# ANALOG-PART.net
KiCad netlist of a schematic drawn in Altium Designer
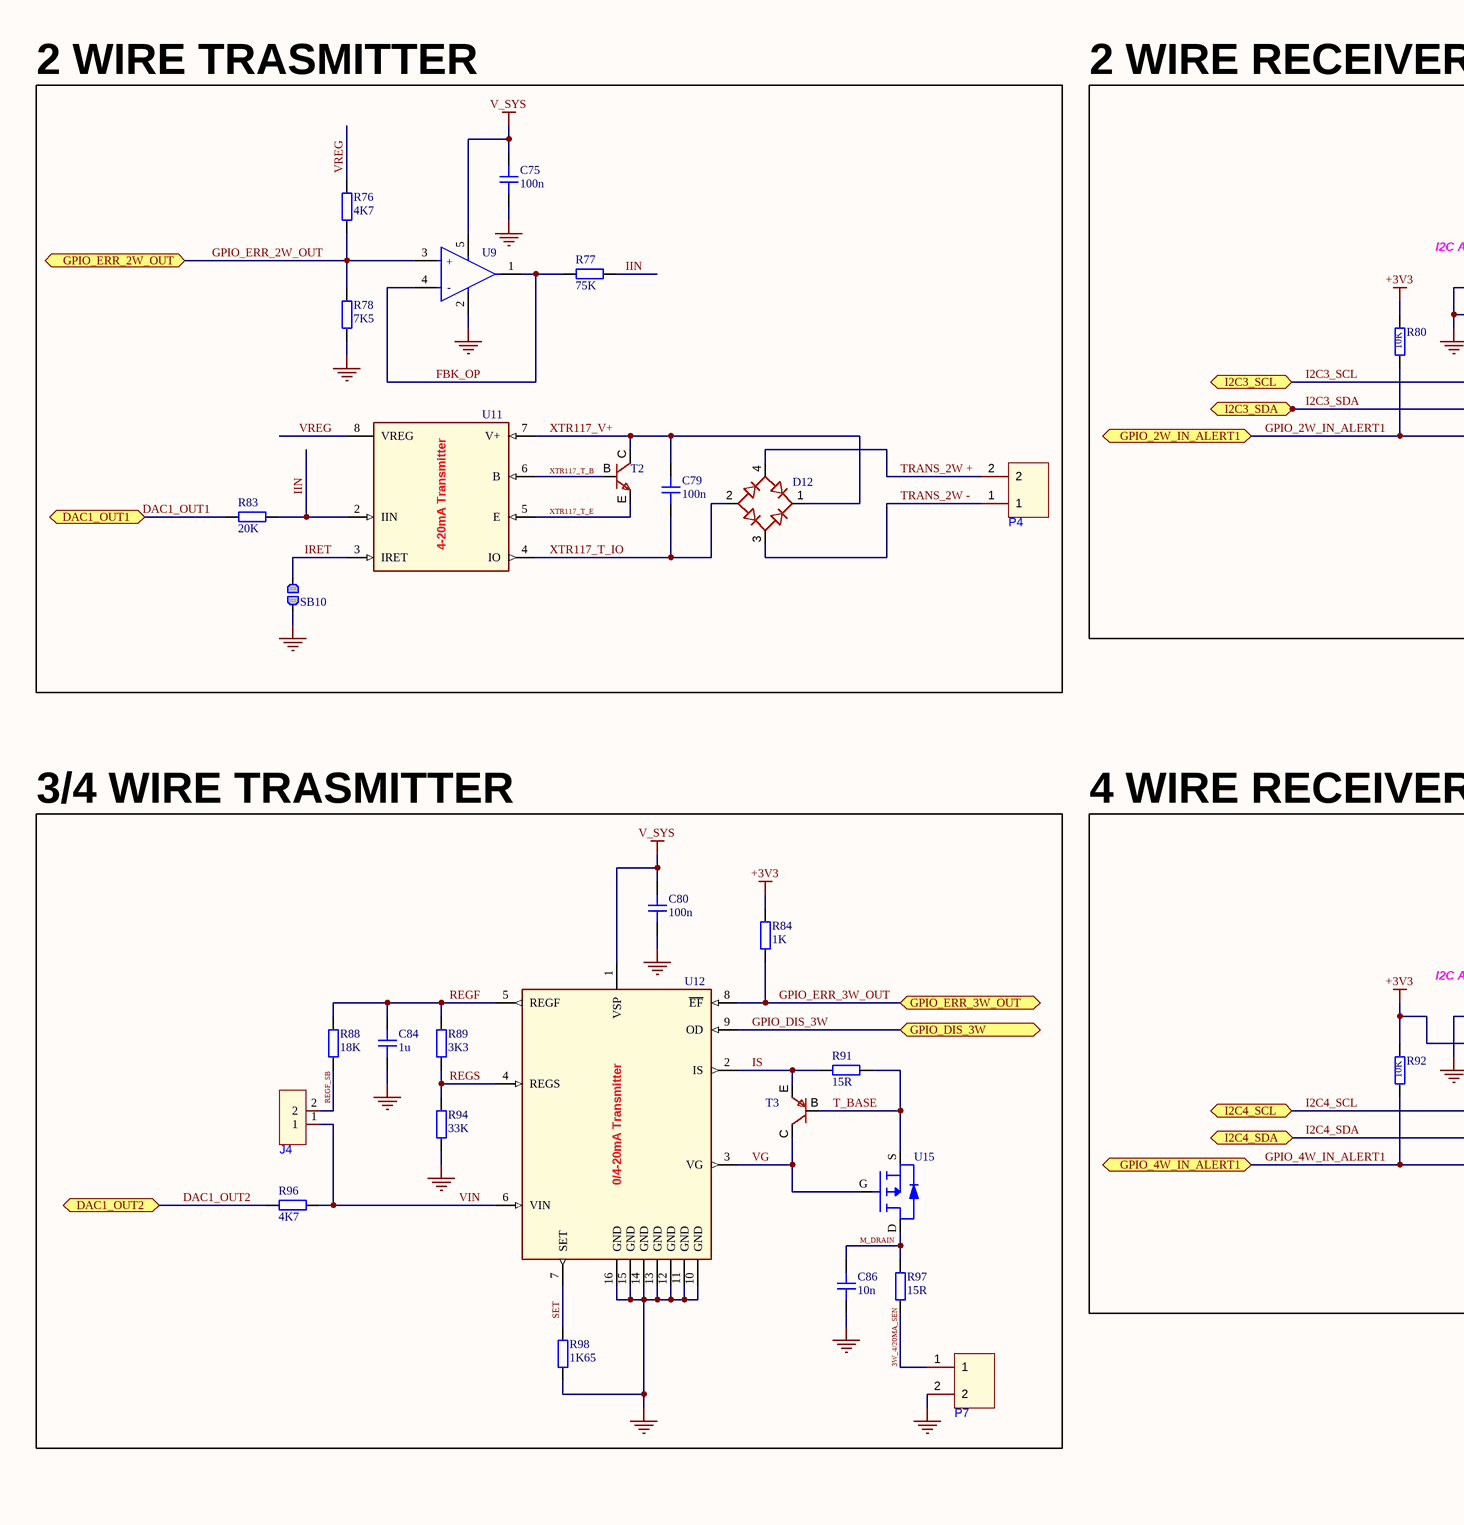
[diagram p0: ANALOG-PART.SchDoc, left]
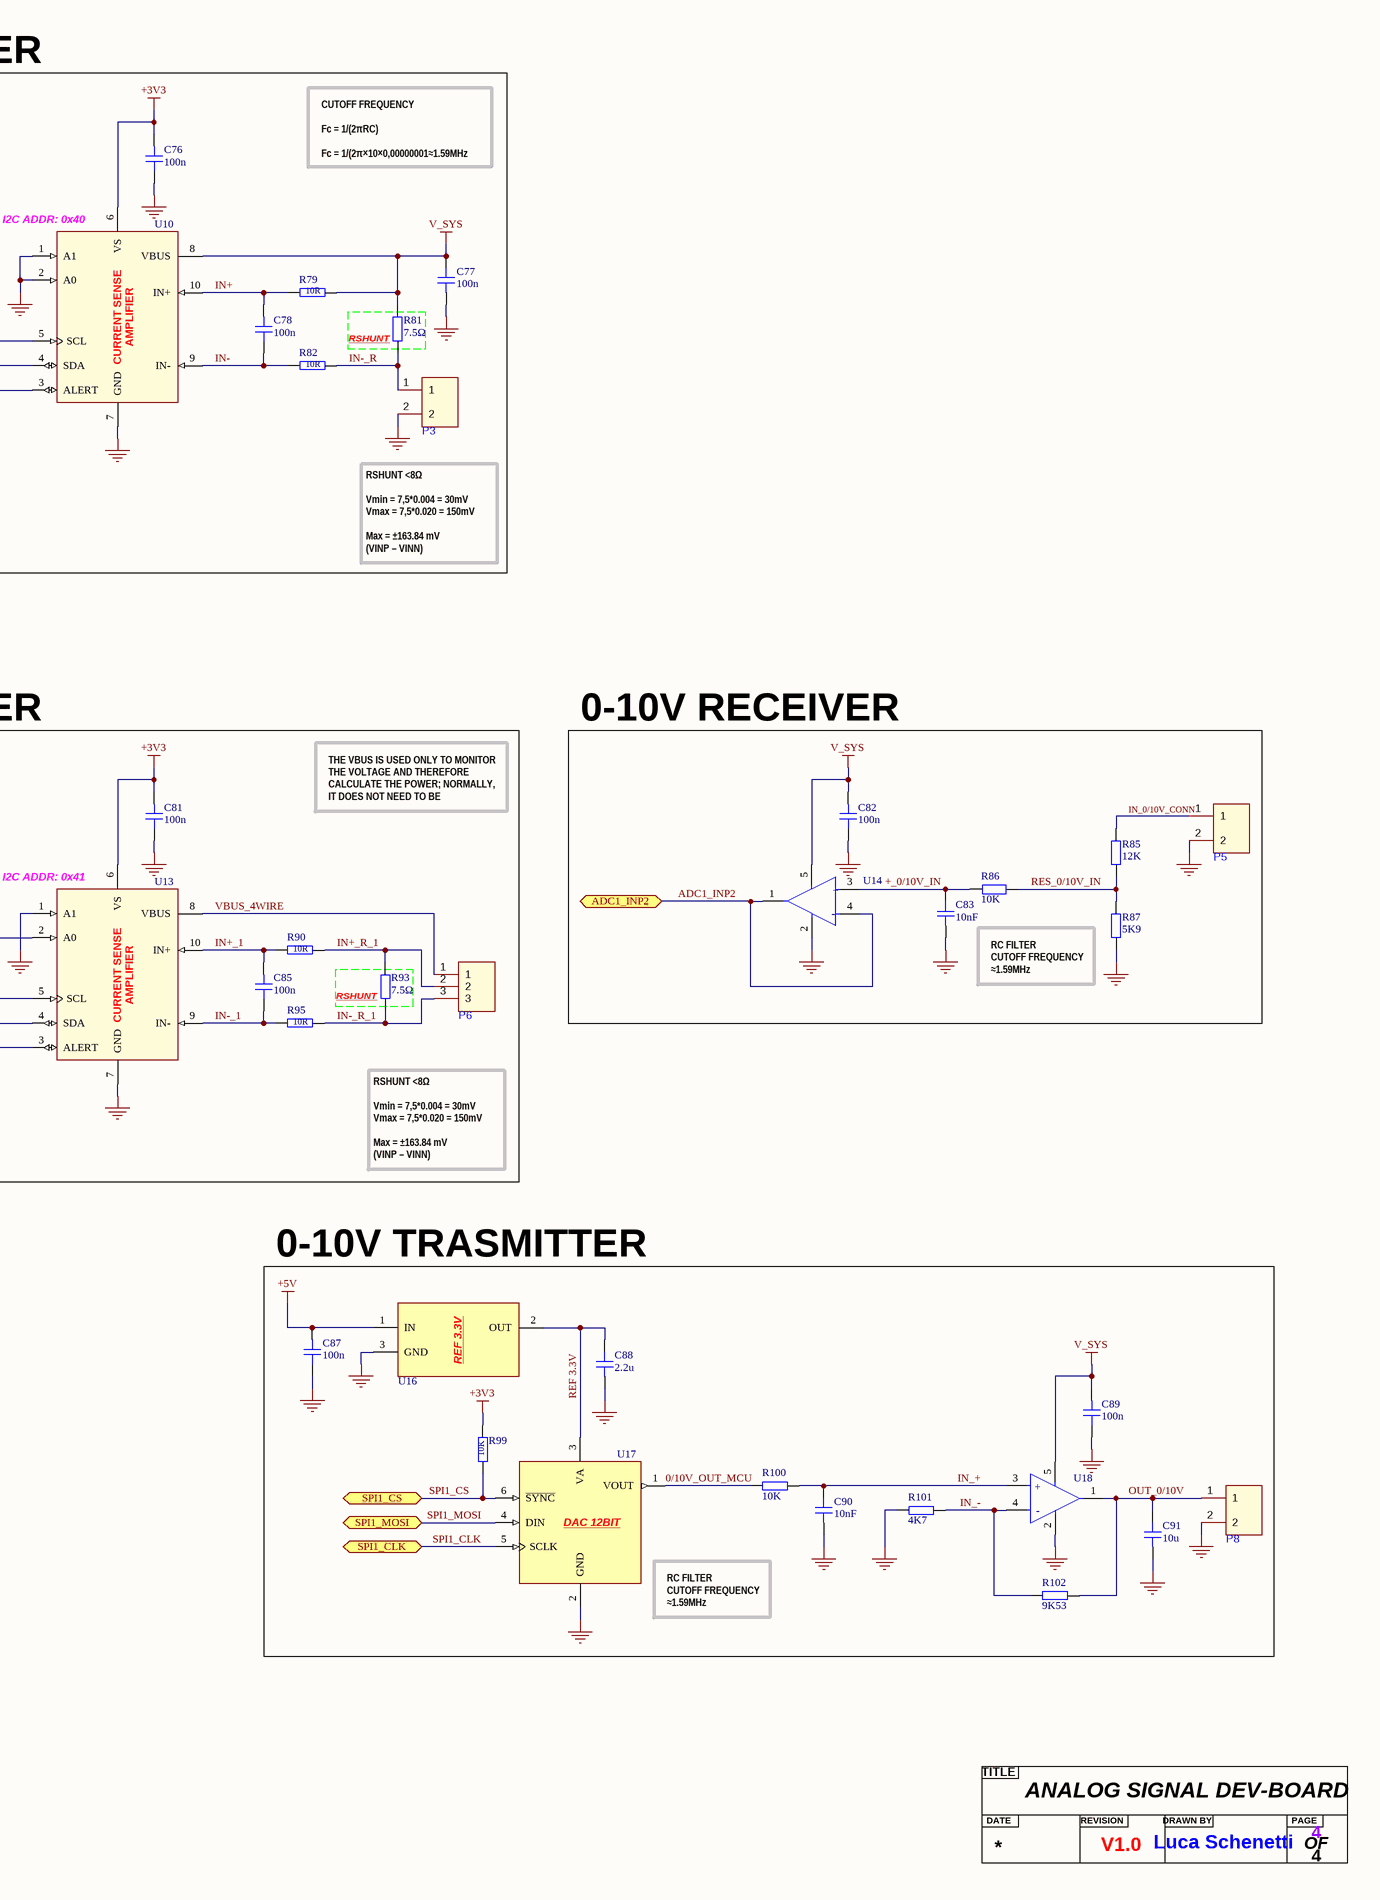
[diagram p1: ANALOG-PART.SchDoc, right]

(export (version "E")
  (design (tool "Eeschema 10.0.6"))
  (components
    (comp (ref "C75")
      (value "100n")
      (footprint "CAP_0603")
      (description "Capacitor SMD 0603 [C14663]")
      (libsource (lib "Schematic-Lib-PhilsLab") (part "CAP_0603"))
    )
    (comp (ref "C76")
      (value "100n")
      (footprint "CAP_0603")
      (description "Capacitor SMD 0603 [C14663]")
      (libsource (lib "Schematic-Lib-PhilsLab") (part "CAP_0603"))
    )
    (comp (ref "C77")
      (value "100n")
      (footprint "CAP_0603")
      (description "Capacitor SMD 0603 [C14663]")
      (libsource (lib "Schematic-Lib-PhilsLab") (part "CAP_0603"))
    )
    (comp (ref "C78")
      (value "100n")
      (footprint "CAP_0603")
      (description "Capacitor SMD 0603 [C14663]")
      (libsource (lib "Schematic-Lib-PhilsLab") (part "CAP_0603"))
    )
    (comp (ref "C79")
      (value "100n")
      (footprint "CAP_0603")
      (description "Capacitor SMD 0603 [C14663]")
      (libsource (lib "Schematic-Lib-PhilsLab") (part "CAP_0603"))
    )
    (comp (ref "C80")
      (value "100n")
      (footprint "CAP_0603")
      (description "Capacitor SMD 0603 [C14663]")
      (libsource (lib "Schematic-Lib-PhilsLab") (part "CAP_0603"))
    )
    (comp (ref "C81")
      (value "100n")
      (footprint "CAP_0603")
      (description "Capacitor SMD 0603 [C14663]")
      (libsource (lib "Schematic-Lib-PhilsLab") (part "CAP_0603"))
    )
    (comp (ref "C82")
      (value "100n")
      (footprint "CAP_0603")
      (description "Capacitor SMD 0603 [C14663]")
      (libsource (lib "Schematic-Lib-PhilsLab") (part "CAP_0603"))
    )
    (comp (ref "C83")
      (value "10nF")
      (footprint "CAP_0603")
      (description "[C302009]")
      (libsource (lib "Schematic-Lib-PhilsLab") (part "CAP_0603"))
    )
    (comp (ref "C84")
      (value "1u")
      (footprint "CAP_0603")
      (description "[C15849]")
      (libsource (lib "Schematic-Lib-PhilsLab") (part "CAP_0603"))
    )
    (comp (ref "C85")
      (value "100n")
      (footprint "CAP_0603")
      (description "Capacitor SMD 0603 [C14663]")
      (libsource (lib "Schematic-Lib-PhilsLab") (part "CAP_0603"))
    )
    (comp (ref "C86")
      (value "10n")
      (footprint "CAP_0603")
      (description "[C302009]")
      (libsource (lib "Schematic-Lib-PhilsLab") (part "CAP_0603"))
    )
    (comp (ref "C87")
      (value "100n")
      (footprint "CAP_0603")
      (description "Capacitor SMD 0603 [C14663]")
      (libsource (lib "Schematic-Lib-PhilsLab") (part "CAP_0603"))
    )
    (comp (ref "C88")
      (value "2.2u")
      (footprint "CAP_0603")
      (description "Capacitor SMD 0603 [C23630]")
      (libsource (lib "Schematic-Lib-PhilsLab") (part "CAP_0603"))
    )
    (comp (ref "C89")
      (value "100n")
      (footprint "CAP_0603")
      (description "Capacitor SMD 0603 [C14663]")
      (libsource (lib "Schematic-Lib-PhilsLab") (part "CAP_0603"))
    )
    (comp (ref "C90")
      (value "10nF")
      (footprint "CAP_0603")
      (description "[C302009]")
      (libsource (lib "Schematic-Lib-PhilsLab") (part "CAP_0603"))
    )
    (comp (ref "C91")
      (value "10u")
      (footprint "CAP_0603")
      (description "[C96446]")
      (libsource (lib "Schematic-Lib-PhilsLab") (part "CAP_0603"))
    )
    (comp (ref "D12")
      (value "MBS Bridge Rectifiers 35A 1.1V")
      (footprint "MB10S")
      (description "[C2488]")
      (libsource (lib "My_Library") (part "MB10S"))
    )
    (comp (ref "J4")
      (value "2.54mm 2P")
      (footprint "2.54mm 2P")
      (description "[C124375]")
      (fields (field (name "MANUFACTURER") "Ckmtw(灿科盟)") (field (name "MANUFACTURER PART") "B-2100S02P-A110"))
      (libsource (lib "My_Library") (part "2.54mm 2P"))
    )
    (comp (ref "P3")
      (value "WJ500V-5.08-2P")
      (footprint "CONN-TH_2P-P5.00_WJ500V-5.08-2P")
      (description "[C8465]")
      (fields (field (name "MANUFACTURER") "KANGNEX(康奈克斯电气)"))
      (libsource (lib "My_Library") (part "WJ500V-5.08-2P"))
    )
    (comp (ref "P4")
      (value "WJ500V-5.08-2P")
      (footprint "CONN-TH_2P-P5.00_WJ500V-5.08-2P")
      (description "[C8465]")
      (fields (field (name "MANUFACTURER") "KANGNEX(康奈克斯电气)"))
      (libsource (lib "") (part "WJ500V-5.08-2P_1"))
    )
    (comp (ref "P5")
      (value "WJ500V-5.08-2P")
      (footprint "CONN-TH_2P-P5.00_WJ500V-5.08-2P")
      (description "[C8465]")
      (fields (field (name "MANUFACTURER") "KANGNEX(康奈克斯电气)"))
      (libsource (lib "My_Library") (part "WJ500V-5.08-2P"))
    )
    (comp (ref "P6")
      (value "WJ500V-5.08-3P")
      (footprint "CONN-TH_3P-P5.00_WJ500V-5.08-3P")
      (description "[C72334]")
      (fields (field (name "MANUFACTURER") "KANGNEX(康奈克斯电气)"))
      (libsource (lib "My_Library") (part "WJ500V-5.08-3P"))
    )
    (comp (ref "P7")
      (value "WJ500V-5.08-2P")
      (footprint "CONN-TH_2P-P5.00_WJ500V-5.08-2P")
      (description "[C8465]")
      (fields (field (name "MANUFACTURER") "KANGNEX(康奈克斯电气)"))
      (libsource (lib "My_Library") (part "WJ500V-5.08-2P"))
    )
    (comp (ref "P8")
      (value "WJ500V-5.08-2P")
      (footprint "CONN-TH_2P-P5.00_WJ500V-5.08-2P")
      (description "[C8465]")
      (fields (field (name "MANUFACTURER") "KANGNEX(康奈克斯电气)"))
      (libsource (lib "My_Library") (part "WJ500V-5.08-2P"))
    )
    (comp (ref "R76")
      (value "4K7")
      (footprint "RES_0603")
      (description "[C105428]")
      (libsource (lib "Schematic-Lib-PhilsLab") (part "RES_0603"))
    )
    (comp (ref "R77")
      (value "75K")
      (footprint "RES_0603")
      (description "[C23242]")
      (libsource (lib "Schematic-Lib-PhilsLab") (part "RES_0603"))
    )
    (comp (ref "R78")
      (value "7K5")
      (footprint "RES_0603")
      (description "[C23234]")
      (libsource (lib "Schematic-Lib-PhilsLab") (part "RES_0603"))
    )
    (comp (ref "R79")
      (value "10R")
      (footprint "RES_0603")
      (description "Resistor SMD 0603 [C22859]")
      (libsource (lib "Schematic-Lib-PhilsLab") (part "RES_0603"))
    )
    (comp (ref "R80")
      (value "10K")
      (footprint "RES_0603")
      (description "[C25804]")
      (libsource (lib "Schematic-Lib-PhilsLab") (part "RES_0603"))
    )
    (comp (ref "R81")
      (value "7.5Ω")
      (footprint "RES_0805")
      (description "[C2828733]")
      (libsource (lib "Schematic-Lib-PhilsLab") (part "RES_0805"))
    )
    (comp (ref "R82")
      (value "10R")
      (footprint "RES_0603")
      (description "Resistor SMD 0603 [C22859]")
      (libsource (lib "Schematic-Lib-PhilsLab") (part "RES_0603"))
    )
    (comp (ref "R83")
      (value "20K")
      (footprint "RES_0603")
      (description "[C4184]")
      (libsource (lib "Schematic-Lib-PhilsLab") (part "RES_0603"))
    )
    (comp (ref "R84")
      (value "1K")
      (footprint "RES_0603")
      (description "[C21190]")
      (libsource (lib "Schematic-Lib-PhilsLab") (part "RES_0603"))
    )
    (comp (ref "R85")
      (value "12K")
      (footprint "RES_0603")
      (description "[C326735]")
      (libsource (lib "Schematic-Lib-PhilsLab") (part "RES_0603"))
    )
    (comp (ref "R86")
      (value "10K")
      (footprint "RES_0603")
      (description "[C25804]")
      (libsource (lib "Schematic-Lib-PhilsLab") (part "RES_0603"))
    )
    (comp (ref "R87")
      (value "5K9")
      (footprint "RES_0603")
      (description "[C491142]")
      (libsource (lib "Schematic-Lib-PhilsLab") (part "RES_0603"))
    )
    (comp (ref "R88")
      (value "18K")
      (footprint "RES_0603")
      (description "[C309650]")
      (libsource (lib "Schematic-Lib-PhilsLab") (part "RES_0603"))
    )
    (comp (ref "R89")
      (value "3K3")
      (footprint "RES_0603")
      (description "[C22978]")
      (libsource (lib "Schematic-Lib-PhilsLab") (part "RES_0603"))
    )
    (comp (ref "R90")
      (value "10R")
      (footprint "RES_0603")
      (description "Resistor SMD 0603 [C22859]")
      (libsource (lib "Schematic-Lib-PhilsLab") (part "RES_0603"))
    )
    (comp (ref "R91")
      (value "15R")
      (footprint "RES_0603")
      (description "[C22810]")
      (libsource (lib "Schematic-Lib-PhilsLab") (part "RES_0603"))
    )
    (comp (ref "R92")
      (value "10K")
      (footprint "RES_0603")
      (description "[C25804]")
      (libsource (lib "Schematic-Lib-PhilsLab") (part "RES_0603"))
    )
    (comp (ref "R93")
      (value "7.5Ω")
      (footprint "RES_0805")
      (description "[C2828733]")
      (libsource (lib "Schematic-Lib-PhilsLab") (part "RES_0805"))
    )
    (comp (ref "R94")
      (value "33K")
      (footprint "RES_0603")
      (description "[C4216]")
      (libsource (lib "Schematic-Lib-PhilsLab") (part "RES_0603"))
    )
    (comp (ref "R95")
      (value "10R")
      (footprint "RES_0603")
      (description "Resistor SMD 0603 [C22859]")
      (libsource (lib "Schematic-Lib-PhilsLab") (part "RES_0603"))
    )
    (comp (ref "R96")
      (value "4K7")
      (footprint "RES_0603")
      (description "[C99782]")
      (libsource (lib "Schematic-Lib-PhilsLab") (part "RES_0603"))
    )
    (comp (ref "R97")
      (value "15R")
      (footprint "RES_0603")
      (description "[C22810]")
      (libsource (lib "Schematic-Lib-PhilsLab") (part "RES_0603"))
    )
    (comp (ref "R98")
      (value "1K65")
      (footprint "RES_0603")
      (description "[C22845]")
      (libsource (lib "Schematic-Lib-PhilsLab") (part "RES_0603"))
    )
    (comp (ref "R99")
      (value "10K")
      (footprint "RES_0603")
      (description "[C25804]")
      (libsource (lib "Schematic-Lib-PhilsLab") (part "RES_0603"))
    )
    (comp (ref "R100")
      (value "10K")
      (footprint "RES_0603")
      (description "[C25804]")
      (libsource (lib "Schematic-Lib-PhilsLab") (part "RES_0603"))
    )
    (comp (ref "R101")
      (value "4K7")
      (footprint "RES_0603")
      (description "[C105428]")
      (libsource (lib "Schematic-Lib-PhilsLab") (part "RES_0603"))
    )
    (comp (ref "R102")
      (value "9K53")
      (footprint "RES_0603")
      (description "[C2960722]")
      (libsource (lib "Schematic-Lib-PhilsLab") (part "RES_0603"))
    )
    (comp (ref "SB10")
      (value "Solderbridge")
      (footprint "PCB_Mechanical:Solderbridge")
      (libsource (lib "SCH_Mechanical") (part "Solderbridge"))
    )
    (comp (ref "T2")
      (value "45V NPN IC = 2A")
      (footprint "FCX690BTA")
      (description "[C460072]")
      (libsource (lib "My_Library") (part "FCX690BTA"))
    )
    (comp (ref "T3")
      (value "25V PNP IC = 1,5A")
      (footprint "SS8550")
      (description "[C7420371]")
      (libsource (lib "My_Library") (part "SS8550"))
    )
    (comp (ref "U9")
      (value "OPA197IDBVR")
      (footprint "FP-DBV0005A-IPC_A")
      (description "IC OPAMP GP 1 CIRCUIT SOT23-5 [C221351]")
      (libsource (lib "Altium Content Vault") (part "1dcd28e651784f0a5a8ed6f8452eeff"))
    )
    (comp (ref "U10")
      (value "Current Sense Amplifiers")
      (footprint "INA237AIDGSR")
      (description "[C2864837]")
      (libsource (lib "My_Library") (part "INA237AIDGSR"))
    )
    (comp (ref "U11")
      (value "4-20mA Current Loop Transmitter")
      (footprint "XTR117AIDGKR")
      (description "[C140927]")
      (libsource (lib "My_Library") (part "XTR117AIDGKR"))
    )
    (comp (ref "U12")
      (value "0/4-20mA Current Loop Transmitter")
      (footprint "XTR111AIDGQR")
      (description "[C26350]")
      (libsource (lib "My_Library") (part "XTR111AIDGQR"))
    )
    (comp (ref "U13")
      (value "Current Sense Amplifiers")
      (footprint "INA237AIDGSR")
      (description "[C2864837]")
      (libsource (lib "My_Library") (part "INA237AIDGSR"))
    )
    (comp (ref "U14")
      (value "OPA197IDBVR")
      (footprint "FP-DBV0005A-IPC_A")
      (description "[C221351]")
      (libsource (lib "Altium Content Vault") (part "1dcd28e651784f0a5a8ed6f8452eeff"))
    )
    (comp (ref "U15")
      (value "P-Channel Mosfet Vds=-60V Vgs=-20V")
      (footprint "SI2309CDS-T1-GE3")
      (description "[C5350873]")
      (libsource (lib "My_Library") (part "SI2309CDS-T1-GE3"))
    )
    (comp (ref "U16")
      (value "REF 3.3V")
      (footprint "REF3033AIDBZR")
      (description "[C36658]")
      (libsource (lib "My_Library") (part "REF3033AIDBZR"))
    )
    (comp (ref "U17")
      (value "DAC 12BIT")
      (footprint "DAC121S101CIMK/NOPB")
      (description "[C81724]")
      (libsource (lib "My_Library") (part "DAC121S101CIMK/NOPB"))
    )
    (comp (ref "U18")
      (value "OPA197IDBVR")
      (footprint "FP-DBV0005A-IPC_A")
      (description "[C221351]")
      (libsource (lib "Altium Content Vault") (part "1dcd28e651784f0a5a8ed6f8452eeff"))
    )
  )
  (nets
    (net (code "1") (name "+3V3") (class "Default")
      (node (ref "C76") (pin "1") (pinfunction "1_1") (pintype "passive"))
      (node (ref "C81") (pin "1") (pinfunction "1_1") (pintype "passive"))
      (node (ref "R80") (pin "2") (pinfunction "2_2") (pintype "passive"))
      (node (ref "R84") (pin "2") (pinfunction "2_2") (pintype "passive"))
      (node (ref "R92") (pin "2") (pinfunction "2_2") (pintype "passive"))
      (node (ref "R99") (pin "2") (pinfunction "2_2") (pintype "passive"))
      (node (ref "U10") (pin "6") (pinfunction "VS_6") (pintype "power_in"))
      (node (ref "U13") (pin "2") (pinfunction "A0_2") (pintype "input"))
      (node (ref "U13") (pin "6") (pinfunction "VS_6") (pintype "power_in"))
    )
    (net (code "2") (name "+5V") (class "Default")
      (node (ref "C87") (pin "1") (pinfunction "1_1") (pintype "passive"))
      (node (ref "U16") (pin "1") (pinfunction "IN_1") (pintype "power_in"))
    )
    (net (code "3") (name "/+_0{slash}10V_IN") (class "Default")
      (node (ref "C83") (pin "2") (pinfunction "2_2") (pintype "passive"))
      (node (ref "R86") (pin "2") (pinfunction "2_2") (pintype "passive"))
      (node (ref "U14") (pin "3") (pinfunction "+IN_3") (pintype "tri_state"))
    )
    (net (code "4") (name "/0{slash}10V_OUT_MCU") (class "Default")
      (node (ref "R100") (pin "1") (pinfunction "1_1") (pintype "passive"))
      (node (ref "U17") (pin "1") (pinfunction "VOUT_1") (pintype "output"))
    )
    (net (code "5") (name "/3W_4{slash}20MA_SEN") (class "Default")
      (node (ref "P7") (pin "1") (pinfunction "1_1") (pintype "passive"))
      (node (ref "R97") (pin "1") (pinfunction "1_1") (pintype "passive"))
    )
    (net (code "6") (name "/ADC1_INP2") (class "Default")
      (node (ref "U14") (pin "1") (pinfunction "OUT_1") (pintype "passive"))
      (node (ref "U14") (pin "4") (pinfunction "-IN_4") (pintype "tri_state"))
    )
    (net (code "7") (name "/DAC1_OUT1") (class "Default")
      (node (ref "R83") (pin "1") (pinfunction "1_1") (pintype "passive"))
    )
    (net (code "8") (name "/DAC1_OUT2") (class "Default")
      (node (ref "R96") (pin "1") (pinfunction "1_1") (pintype "passive"))
    )
    (net (code "9") (name "/FBK_OP") (class "Default")
      (node (ref "R77") (pin "1") (pinfunction "1_1") (pintype "passive"))
      (node (ref "U9") (pin "1") (pinfunction "OUT_1") (pintype "passive"))
      (node (ref "U9") (pin "4") (pinfunction "-IN_4") (pintype "tri_state"))
    )
    (net (code "10") (name "/GPIO_2W_IN_ALERT1") (class "Default")
      (node (ref "R80") (pin "1") (pinfunction "1_1") (pintype "passive"))
      (node (ref "U10") (pin "3") (pinfunction "ALERT_3") (pintype "bidirectional"))
    )
    (net (code "11") (name "/GPIO_4W_IN_ALERT1") (class "Default")
      (node (ref "R92") (pin "1") (pinfunction "1_1") (pintype "passive"))
      (node (ref "U13") (pin "3") (pinfunction "ALERT_3") (pintype "bidirectional"))
    )
    (net (code "12") (name "/GPIO_DIS_3W") (class "Default")
      (node (ref "U12") (pin "9") (pinfunction "OD_9") (pintype "input"))
    )
    (net (code "13") (name "/GPIO_ERR_2W_OUT") (class "Default")
      (node (ref "R76") (pin "1") (pinfunction "1_1") (pintype "passive"))
      (node (ref "R78") (pin "2") (pinfunction "2_2") (pintype "passive"))
      (node (ref "U9") (pin "3") (pinfunction "+IN_3") (pintype "tri_state"))
    )
    (net (code "14") (name "/GPIO_ERR_3W_OUT") (class "Default")
      (node (ref "R84") (pin "1") (pinfunction "1_1") (pintype "passive"))
      (node (ref "U12") (pin "8") (pinfunction "~{EF}_8") (pintype "input"))
    )
    (net (code "15") (name "/I2C3_SCL") (class "Default")
      (node (ref "U10") (pin "5") (pinfunction "SCL_5") (pintype "input"))
    )
    (net (code "16") (name "/I2C3_SDA") (class "Default")
      (node (ref "U10") (pin "4") (pinfunction "SDA_4") (pintype "bidirectional"))
    )
    (net (code "17") (name "/I2C4_SCL") (class "Default")
      (node (ref "U13") (pin "5") (pinfunction "SCL_5") (pintype "input"))
    )
    (net (code "18") (name "/I2C4_SDA") (class "Default")
      (node (ref "U13") (pin "4") (pinfunction "SDA_4") (pintype "bidirectional"))
    )
    (net (code "19") (name "/IIN") (class "Default")
      (node (ref "R77") (pin "2") (pinfunction "2_2") (pintype "passive"))
      (node (ref "R83") (pin "2") (pinfunction "2_2") (pintype "passive"))
      (node (ref "U11") (pin "2") (pinfunction "IIN_2") (pintype "input"))
    )
    (net (code "20") (name "/IN+") (class "Default")
      (node (ref "C78") (pin "1") (pinfunction "1_1") (pintype "passive"))
      (node (ref "R79") (pin "1") (pinfunction "1_1") (pintype "passive"))
      (node (ref "U10") (pin "10") (pinfunction "IN+_10") (pintype "input"))
    )
    (net (code "21") (name "/IN+_1") (class "Default")
      (node (ref "C85") (pin "1") (pinfunction "1_1") (pintype "passive"))
      (node (ref "R90") (pin "1") (pinfunction "1_1") (pintype "passive"))
      (node (ref "U13") (pin "10") (pinfunction "IN+_10") (pintype "input"))
    )
    (net (code "22") (name "/IN+_R_1") (class "Default")
      (node (ref "P6") (pin "2") (pinfunction "2_2") (pintype "passive"))
      (node (ref "R90") (pin "2") (pinfunction "2_2") (pintype "passive"))
      (node (ref "R93") (pin "2") (pinfunction "2_2") (pintype "passive"))
    )
    (net (code "23") (name "/IN-") (class "Default")
      (node (ref "C78") (pin "2") (pinfunction "2_2") (pintype "passive"))
      (node (ref "R82") (pin "1") (pinfunction "1_1") (pintype "passive"))
      (node (ref "U10") (pin "9") (pinfunction "IN-_9") (pintype "input"))
    )
    (net (code "24") (name "/IN-_1") (class "Default")
      (node (ref "C85") (pin "2") (pinfunction "2_2") (pintype "passive"))
      (node (ref "R95") (pin "1") (pinfunction "1_1") (pintype "passive"))
      (node (ref "U13") (pin "9") (pinfunction "IN-_9") (pintype "input"))
    )
    (net (code "25") (name "/IN-_R") (class "Default")
      (node (ref "P3") (pin "1") (pinfunction "1_1") (pintype "passive"))
      (node (ref "R81") (pin "1") (pinfunction "1_1") (pintype "passive"))
      (node (ref "R82") (pin "2") (pinfunction "2_2") (pintype "passive"))
    )
    (net (code "26") (name "/IN-_R_1") (class "Default")
      (node (ref "P6") (pin "3") (pinfunction "3_3") (pintype "passive"))
      (node (ref "R93") (pin "1") (pinfunction "1_1") (pintype "passive"))
      (node (ref "R95") (pin "2") (pinfunction "2_2") (pintype "passive"))
    )
    (net (code "27") (name "/IN_+") (class "Default")
      (node (ref "C90") (pin "2") (pinfunction "2_2") (pintype "passive"))
      (node (ref "R100") (pin "2") (pinfunction "2_2") (pintype "passive"))
      (node (ref "U18") (pin "3") (pinfunction "+IN_3") (pintype "tri_state"))
    )
    (net (code "28") (name "/IN_-") (class "Default")
      (node (ref "R101") (pin "2") (pinfunction "2_2") (pintype "passive"))
      (node (ref "R102") (pin "1") (pinfunction "1_1") (pintype "passive"))
      (node (ref "U18") (pin "4") (pinfunction "-IN_4") (pintype "tri_state"))
    )
    (net (code "29") (name "/IN_0{slash}10V_CONN") (class "Default")
      (node (ref "P5") (pin "1") (pinfunction "1_1") (pintype "passive"))
      (node (ref "R85") (pin "2") (pinfunction "2_2") (pintype "passive"))
    )
    (net (code "30") (name "/IRET") (class "Default")
      (node (ref "SB10") (pin "2") (pinfunction "2_2") (pintype "passive"))
      (node (ref "U11") (pin "3") (pinfunction "IRET_3") (pintype "input"))
    )
    (net (code "31") (name "/IS") (class "Default")
      (node (ref "R91") (pin "1") (pinfunction "1_1") (pintype "passive"))
      (node (ref "T3") (pin "E") (pinfunction "E_E") (pintype "passive"))
      (node (ref "U12") (pin "2") (pinfunction "IS_2") (pintype "output"))
    )
    (net (code "32") (name "/M_DRAIN") (class "Default")
      (node (ref "C86") (pin "1") (pinfunction "1_1") (pintype "passive"))
      (node (ref "R97") (pin "2") (pinfunction "2_2") (pintype "passive"))
      (node (ref "U15") (pin "D") (pinfunction "D_D") (pintype "passive"))
    )
    (net (code "33") (name "/OUT_0{slash}10V") (class "Default")
      (node (ref "C91") (pin "2") (pinfunction "2_2") (pintype "passive"))
      (node (ref "P8") (pin "1") (pinfunction "1_1") (pintype "passive"))
      (node (ref "R102") (pin "2") (pinfunction "2_2") (pintype "passive"))
      (node (ref "U18") (pin "1") (pinfunction "OUT_1") (pintype "passive"))
    )
    (net (code "34") (name "/REF 3.3V") (class "Default")
      (node (ref "C88") (pin "2") (pinfunction "2_2") (pintype "passive"))
      (node (ref "U16") (pin "2") (pinfunction "OUT_2") (pintype "passive"))
      (node (ref "U17") (pin "3") (pinfunction "VA_3") (pintype "power_in"))
    )
    (net (code "35") (name "/REGF") (class "Default")
      (node (ref "C84") (pin "1") (pinfunction "1_1") (pintype "passive"))
      (node (ref "R88") (pin "2") (pinfunction "2_2") (pintype "passive"))
      (node (ref "R89") (pin "2") (pinfunction "2_2") (pintype "passive"))
      (node (ref "U12") (pin "5") (pinfunction "REGF_5") (pintype "output"))
    )
    (net (code "36") (name "/REGF_SB") (class "Default")
      (node (ref "J4") (pin "2") (pinfunction "2_2") (pintype "passive"))
      (node (ref "R88") (pin "1") (pinfunction "1_1") (pintype "passive"))
    )
    (net (code "37") (name "/REGS") (class "Default")
      (node (ref "R89") (pin "1") (pinfunction "1_1") (pintype "passive"))
      (node (ref "R94") (pin "1") (pinfunction "1_1") (pintype "passive"))
      (node (ref "U12") (pin "4") (pinfunction "REGS_4") (pintype "input"))
    )
    (net (code "38") (name "/RES_0{slash}10V_IN") (class "Default")
      (node (ref "R85") (pin "1") (pinfunction "1_1") (pintype "passive"))
      (node (ref "R86") (pin "1") (pinfunction "1_1") (pintype "passive"))
      (node (ref "R87") (pin "2") (pinfunction "2_2") (pintype "passive"))
    )
    (net (code "39") (name "/SET") (class "Default")
      (node (ref "R98") (pin "2") (pinfunction "2_2") (pintype "passive"))
      (node (ref "U12") (pin "7") (pinfunction "SET_7") (pintype "output"))
    )
    (net (code "40") (name "/SPI1_CLK") (class "Default")
      (node (ref "U17") (pin "5") (pinfunction "SCLK_5") (pintype "input"))
    )
    (net (code "41") (name "/SPI1_CS") (class "Default")
      (node (ref "R99") (pin "1") (pinfunction "1_1") (pintype "passive"))
      (node (ref "U17") (pin "6") (pinfunction "~{SYNC}_6") (pintype "input"))
    )
    (net (code "42") (name "/SPI1_MOSI") (class "Default")
      (node (ref "U17") (pin "4") (pinfunction "DIN_4") (pintype "input"))
    )
    (net (code "43") (name "/TRANS_2W +") (class "Default")
      (node (ref "D12") (pin "4") (pinfunction "AC1_4") (pintype "passive"))
      (node (ref "P4") (pin "2") (pinfunction "2_2") (pintype "passive"))
    )
    (net (code "44") (name "/TRANS_2W -") (class "Default")
      (node (ref "D12") (pin "3") (pinfunction "AC2_3") (pintype "passive"))
      (node (ref "P4") (pin "1") (pinfunction "1_1") (pintype "passive"))
    )
    (net (code "45") (name "/T_BASE") (class "Default")
      (node (ref "R91") (pin "2") (pinfunction "2_2") (pintype "passive"))
      (node (ref "T3") (pin "B") (pinfunction "B_B") (pintype "passive"))
      (node (ref "U15") (pin "S") (pinfunction "S_S") (pintype "passive"))
    )
    (net (code "46") (name "/VBUS_4WIRE") (class "Default")
      (node (ref "P6") (pin "1") (pinfunction "1_1") (pintype "passive"))
      (node (ref "U13") (pin "8") (pinfunction "VBUS_8") (pintype "power_in"))
    )
    (net (code "47") (name "/VG") (class "Default")
      (node (ref "T3") (pin "C") (pinfunction "C_C") (pintype "passive"))
      (node (ref "U12") (pin "3") (pinfunction "VG_3") (pintype "output"))
      (node (ref "U15") (pin "G") (pinfunction "G_G") (pintype "passive"))
    )
    (net (code "48") (name "/VIN") (class "Default")
      (node (ref "J4") (pin "1") (pinfunction "1_1") (pintype "passive"))
      (node (ref "R96") (pin "2") (pinfunction "2_2") (pintype "passive"))
      (node (ref "U12") (pin "6") (pinfunction "VIN_6") (pintype "input"))
    )
    (net (code "49") (name "/VREG") (class "Default")
      (node (ref "R76") (pin "2") (pinfunction "2_2") (pintype "passive"))
      (node (ref "U11") (pin "8") (pinfunction "VREG_8") (pintype "power_in"))
    )
    (net (code "50") (name "/XTR117_T_B") (class "Default")
      (node (ref "T2") (pin "B") (pinfunction "B_B") (pintype "passive"))
      (node (ref "U11") (pin "6") (pinfunction "B_6") (pintype "input"))
    )
    (net (code "51") (name "/XTR117_T_E") (class "Default")
      (node (ref "T2") (pin "E") (pinfunction "E_E") (pintype "passive"))
      (node (ref "U11") (pin "5") (pinfunction "E_5") (pintype "input"))
    )
    (net (code "52") (name "/XTR117_T_IO") (class "Default")
      (node (ref "C79") (pin "2") (pinfunction "2_2") (pintype "passive"))
      (node (ref "D12") (pin "2") (pinfunction "NEG_2") (pintype "passive"))
      (node (ref "U11") (pin "4") (pinfunction "IO_4") (pintype "output"))
    )
    (net (code "53") (name "/XTR117_V+") (class "Default")
      (node (ref "C79") (pin "1") (pinfunction "1_1") (pintype "passive"))
      (node (ref "D12") (pin "1") (pinfunction "POS_1") (pintype "passive"))
      (node (ref "T2") (pin "C") (pinfunction "C_C") (pintype "passive"))
      (node (ref "U11") (pin "7") (pinfunction "V+_7") (pintype "input"))
    )
    (net (code "54") (name "GND") (class "Default")
      (node (ref "C75") (pin "2") (pinfunction "2_2") (pintype "passive"))
      (node (ref "C76") (pin "2") (pinfunction "2_2") (pintype "passive"))
      (node (ref "C77") (pin "1") (pinfunction "1_1") (pintype "passive"))
      (node (ref "C80") (pin "2") (pinfunction "2_2") (pintype "passive"))
      (node (ref "C81") (pin "2") (pinfunction "2_2") (pintype "passive"))
      (node (ref "C82") (pin "2") (pinfunction "2_2") (pintype "passive"))
      (node (ref "C83") (pin "1") (pinfunction "1_1") (pintype "passive"))
      (node (ref "C84") (pin "2") (pinfunction "2_2") (pintype "passive"))
      (node (ref "C86") (pin "2") (pinfunction "2_2") (pintype "passive"))
      (node (ref "C87") (pin "2") (pinfunction "2_2") (pintype "passive"))
      (node (ref "C88") (pin "1") (pinfunction "1_1") (pintype "passive"))
      (node (ref "C89") (pin "2") (pinfunction "2_2") (pintype "passive"))
      (node (ref "C90") (pin "1") (pinfunction "1_1") (pintype "passive"))
      (node (ref "C91") (pin "1") (pinfunction "1_1") (pintype "passive"))
      (node (ref "P3") (pin "2") (pinfunction "2_2") (pintype "passive"))
      (node (ref "P5") (pin "2") (pinfunction "2_2") (pintype "passive"))
      (node (ref "P7") (pin "2") (pinfunction "2_2") (pintype "passive"))
      (node (ref "P8") (pin "2") (pinfunction "2_2") (pintype "passive"))
      (node (ref "R101") (pin "1") (pinfunction "1_1") (pintype "passive"))
      (node (ref "R78") (pin "1") (pinfunction "1_1") (pintype "passive"))
      (node (ref "R87") (pin "1") (pinfunction "1_1") (pintype "passive"))
      (node (ref "R94") (pin "2") (pinfunction "2_2") (pintype "passive"))
      (node (ref "R98") (pin "1") (pinfunction "1_1") (pintype "passive"))
      (node (ref "SB10") (pin "1") (pinfunction "1_1") (pintype "passive"))
      (node (ref "U10") (pin "1") (pinfunction "A1_1") (pintype "input"))
      (node (ref "U10") (pin "2") (pinfunction "A0_2") (pintype "input"))
      (node (ref "U10") (pin "7") (pinfunction "GND_7") (pintype "power_in"))
      (node (ref "U12") (pin "10") (pinfunction "GND_10") (pintype "power_in"))
      (node (ref "U12") (pin "11") (pinfunction "GND_11") (pintype "power_in"))
      (node (ref "U12") (pin "12") (pinfunction "GND_12") (pintype "power_in"))
      (node (ref "U12") (pin "13") (pinfunction "GND_13") (pintype "power_in"))
      (node (ref "U12") (pin "14") (pinfunction "GND_14") (pintype "power_in"))
      (node (ref "U12") (pin "15") (pinfunction "GND_15") (pintype "power_in"))
      (node (ref "U12") (pin "16") (pinfunction "GND_16") (pintype "power_in"))
      (node (ref "U13") (pin "1") (pinfunction "A1_1") (pintype "input"))
      (node (ref "U13") (pin "7") (pinfunction "GND_7") (pintype "power_in"))
      (node (ref "U14") (pin "2") (pinfunction "V-_2") (pintype "power_in"))
      (node (ref "U16") (pin "3") (pinfunction "GND_3") (pintype "passive"))
      (node (ref "U17") (pin "2") (pinfunction "GND_2") (pintype "power_in"))
      (node (ref "U18") (pin "2") (pinfunction "V-_2") (pintype "power_in"))
      (node (ref "U9") (pin "2") (pinfunction "V-_2") (pintype "power_in"))
    )
    (net (code "55") (name "V_SYS") (class "Default")
      (node (ref "C75") (pin "1") (pinfunction "1_1") (pintype "passive"))
      (node (ref "C77") (pin "2") (pinfunction "2_2") (pintype "passive"))
      (node (ref "C80") (pin "1") (pinfunction "1_1") (pintype "passive"))
      (node (ref "C82") (pin "1") (pinfunction "1_1") (pintype "passive"))
      (node (ref "C89") (pin "1") (pinfunction "1_1") (pintype "passive"))
      (node (ref "R79") (pin "2") (pinfunction "2_2") (pintype "passive"))
      (node (ref "R81") (pin "2") (pinfunction "2_2") (pintype "passive"))
      (node (ref "U10") (pin "8") (pinfunction "VBUS_8") (pintype "power_in"))
      (node (ref "U12") (pin "1") (pinfunction "VSP_1") (pintype "power_in"))
      (node (ref "U14") (pin "5") (pinfunction "V+_5") (pintype "power_in"))
      (node (ref "U18") (pin "5") (pinfunction "V+_5") (pintype "power_in"))
      (node (ref "U9") (pin "5") (pinfunction "V+_5") (pintype "power_in"))
    )
  )
)
